# WiFi-Bee_v11.net
KiCad netlist of a schematic drawn in EAGLE
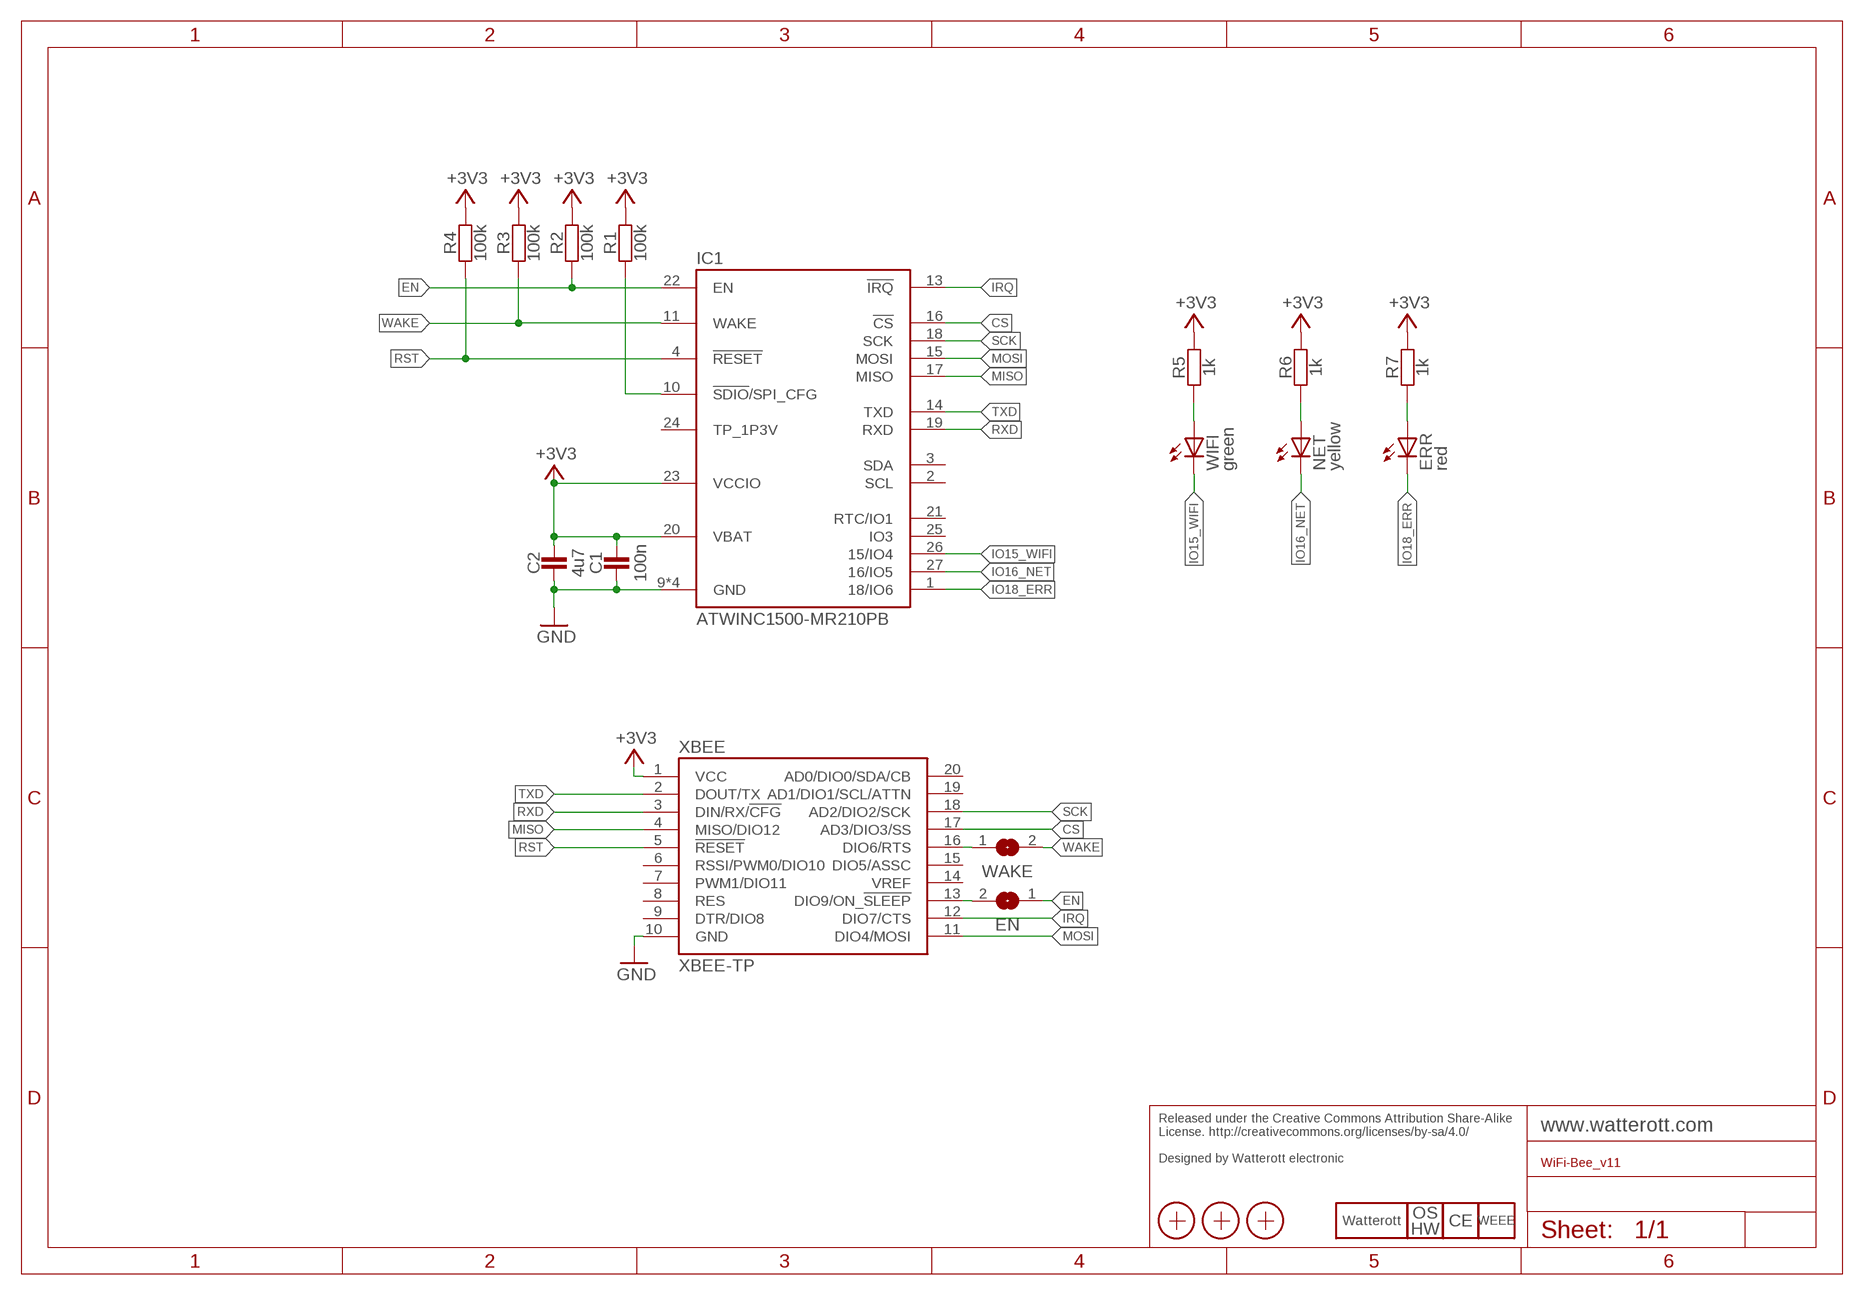
[diagram p0: schematic, sheet 1]

(export (version "E")
  (design (tool "Eeschema 10.0.6"))
  (components
    (comp (ref "C1")
      (value "100n")
      (footprint "eagle-import:C0402")
      (libsource (lib "eagle-import") (part "CAPACITOR-0402"))
    )
    (comp (ref "C2")
      (value "4u7")
      (footprint "eagle-import:C0402")
      (libsource (lib "eagle-import") (part "CAPACITOR-0402"))
    )
    (comp (ref "EN")
      (value "JUMPER2-0402")
      (footprint "eagle-import:JUMPER2-0402")
      (libsource (lib "eagle-import") (part "JUMPER2-0402"))
    )
    (comp (ref "ERR")
      (value "red")
      (footprint "eagle-import:C0603")
      (libsource (lib "eagle-import") (part "LED-0603"))
    )
    (comp (ref "IC1")
      (value "ATWINC1500-MR210PB")
      (footprint "eagle-import:ATWINC1500-MX210")
      (libsource (lib "eagle-import") (part "ATWINC1500-MR210PB"))
    )
    (comp (ref "LOGO1")
      (value "LOGO_CE-2")
      (footprint "eagle-import:CE_2MM")
      (libsource (lib "eagle-import") (part "LOGO_CE-2"))
    )
    (comp (ref "LOGO2")
      (value "LOGO_WEEE-4")
      (footprint "eagle-import:WEEE_4MM")
      (libsource (lib "eagle-import") (part "LOGO_WEEE-4"))
    )
    (comp (ref "LOGO3")
      (value "LOGO_SPARK-2")
      (footprint "eagle-import:SPARK_2MM")
      (libsource (lib "eagle-import") (part "LOGO_SPARK-2"))
    )
    (comp (ref "LOGO4")
      (value "LOGO_OSHW-2")
      (footprint "eagle-import:OSHW_2MM")
      (libsource (lib "eagle-import") (part "LOGO_OSHW-2"))
    )
    (comp (ref "NET")
      (value "yellow")
      (footprint "eagle-import:C0603")
      (libsource (lib "eagle-import") (part "LED-0603"))
    )
    (comp (ref "R1")
      (value "100k")
      (footprint "eagle-import:C0402")
      (libsource (lib "eagle-import") (part "RESISTOR-0402"))
    )
    (comp (ref "R2")
      (value "100k")
      (footprint "eagle-import:C0402")
      (libsource (lib "eagle-import") (part "RESISTOR-0402"))
    )
    (comp (ref "R3")
      (value "100k")
      (footprint "eagle-import:C0402")
      (libsource (lib "eagle-import") (part "RESISTOR-0402"))
    )
    (comp (ref "R4")
      (value "100k")
      (footprint "eagle-import:C0402")
      (libsource (lib "eagle-import") (part "RESISTOR-0402"))
    )
    (comp (ref "R5")
      (value "1k")
      (footprint "eagle-import:C0402")
      (libsource (lib "eagle-import") (part "RESISTOR-0402"))
    )
    (comp (ref "R6")
      (value "1k")
      (footprint "eagle-import:C0402")
      (libsource (lib "eagle-import") (part "RESISTOR-0402"))
    )
    (comp (ref "R7")
      (value "1k")
      (footprint "eagle-import:C0402")
      (libsource (lib "eagle-import") (part "RESISTOR-0402"))
    )
    (comp (ref "WAKE")
      (value "JUMPER2-0402")
      (footprint "eagle-import:JUMPER2-0402")
      (libsource (lib "eagle-import") (part "JUMPER2-0402"))
    )
    (comp (ref "WIFI")
      (value "green")
      (footprint "eagle-import:C0603")
      (libsource (lib "eagle-import") (part "LED-0603"))
    )
    (comp (ref "X1")
      (value "PASSER-07")
      (footprint "eagle-import:PASSER_07MM")
      (libsource (lib "eagle-import") (part "PASSER-07"))
    )
    (comp (ref "X2")
      (value "PASSER-07")
      (footprint "eagle-import:PASSER_07MM")
      (libsource (lib "eagle-import") (part "PASSER-07"))
    )
    (comp (ref "X3")
      (value "PASSER-07")
      (footprint "eagle-import:PASSER_07MM")
      (libsource (lib "eagle-import") (part "PASSER-07"))
    )
    (comp (ref "XBEE")
      (value "XBEE-TP")
      (footprint "eagle-import:XBEE_TP")
      (libsource (lib "eagle-import") (part "XBEE-TP"))
    )
  )
  (nets
    (net (code "1") (name "+3V3") (class "Default")
      (node (ref "C1") (pin "2") (pinfunction "2_2") (pintype "passive"))
      (node (ref "C2") (pin "2") (pinfunction "2_2") (pintype "passive"))
      (node (ref "IC1") (pin "20") (pinfunction "VBAT_20") (pintype "power_in"))
      (node (ref "IC1") (pin "23") (pinfunction "VCCIO_23") (pintype "power_in"))
      (node (ref "R1") (pin "2") (pinfunction "2_2") (pintype "passive"))
      (node (ref "R2") (pin "2") (pinfunction "2_2") (pintype "passive"))
      (node (ref "R3") (pin "2") (pinfunction "2_2") (pintype "passive"))
      (node (ref "R4") (pin "2") (pinfunction "2_2") (pintype "passive"))
      (node (ref "R5") (pin "2") (pinfunction "2_2") (pintype "passive"))
      (node (ref "R6") (pin "2") (pinfunction "2_2") (pintype "passive"))
      (node (ref "R7") (pin "2") (pinfunction "2_2") (pintype "passive"))
      (node (ref "XBEE") (pin "1") (pinfunction "VCC_1") (pintype "power_in"))
    )
    (net (code "2") (name "CS") (class "Default")
      (node (ref "IC1") (pin "16") (pinfunction "~{CS}_16") (pintype "input"))
      (node (ref "XBEE") (pin "17") (pinfunction "AD3/DIO3/SS_17") (pintype "bidirectional"))
    )
    (net (code "3") (name "EN") (class "Default")
      (node (ref "EN") (pin "1") (pinfunction "1_1") (pintype "passive"))
      (node (ref "IC1") (pin "22") (pinfunction "EN_22") (pintype "input"))
      (node (ref "R2") (pin "1") (pinfunction "1_1") (pintype "passive"))
    )
    (net (code "4") (name "GND") (class "Default")
      (node (ref "C1") (pin "1") (pinfunction "1_1") (pintype "passive"))
      (node (ref "C2") (pin "1") (pinfunction "1_1") (pintype "passive"))
      (node (ref "IC1") (pin "12") (pinfunction "GND_12") (pintype "power_in"))
      (node (ref "IC1") (pin "28") (pinfunction "GND_28") (pintype "power_in"))
      (node (ref "IC1") (pin "9") (pinfunction "GND_9") (pintype "power_in"))
      (node (ref "IC1") (pin "GND") (pinfunction "GND_GND") (pintype "power_in"))
      (node (ref "XBEE") (pin "10") (pinfunction "GND_10") (pintype "power_in"))
    )
    (net (code "5") (name "IO15_WIFI") (class "Default")
      (node (ref "IC1") (pin "26") (pinfunction "15/IO4_26") (pintype "bidirectional"))
      (node (ref "WIFI") (pin "C") (pinfunction "C_C") (pintype "passive"))
    )
    (net (code "6") (name "IO16_NET") (class "Default")
      (node (ref "IC1") (pin "27") (pinfunction "16/IO5_27") (pintype "bidirectional"))
      (node (ref "NET") (pin "C") (pinfunction "C_C") (pintype "passive"))
    )
    (net (code "7") (name "IO18_ERR") (class "Default")
      (node (ref "ERR") (pin "C") (pinfunction "C_C") (pintype "passive"))
      (node (ref "IC1") (pin "1") (pinfunction "18/IO6_1") (pintype "bidirectional"))
    )
    (net (code "8") (name "IRQ") (class "Default")
      (node (ref "IC1") (pin "13") (pinfunction "~{IRQ}_13") (pintype "output"))
      (node (ref "XBEE") (pin "12") (pinfunction "DIO7/CTS_12") (pintype "bidirectional"))
    )
    (net (code "9") (name "MISO") (class "Default")
      (node (ref "IC1") (pin "17") (pinfunction "MISO_17") (pintype "output"))
      (node (ref "XBEE") (pin "4") (pinfunction "MISO/DIO12_4") (pintype "bidirectional"))
    )
    (net (code "10") (name "MOSI") (class "Default")
      (node (ref "IC1") (pin "15") (pinfunction "MOSI_15") (pintype "input"))
      (node (ref "XBEE") (pin "11") (pinfunction "DIO4/MOSI_11") (pintype "bidirectional"))
    )
    (net (code "11") (name "Net-(ERR-PadA)") (class "Default")
      (node (ref "ERR") (pin "A") (pinfunction "A_A") (pintype "passive"))
      (node (ref "R7") (pin "1") (pinfunction "1_1") (pintype "passive"))
    )
    (net (code "12") (name "Net-(IC1-~{SDIO}{slash}SPI_CFG)") (class "Default")
      (node (ref "IC1") (pin "10") (pinfunction "~{SDIO}/SPI_CFG_10") (pintype "input"))
      (node (ref "R1") (pin "1") (pinfunction "1_1") (pintype "passive"))
    )
    (net (code "13") (name "Net-(NET-PadA)") (class "Default")
      (node (ref "NET") (pin "A") (pinfunction "A_A") (pintype "passive"))
      (node (ref "R6") (pin "1") (pinfunction "1_1") (pintype "passive"))
    )
    (net (code "14") (name "Net-(R5-Pad1)") (class "Default")
      (node (ref "R5") (pin "1") (pinfunction "1_1") (pintype "passive"))
      (node (ref "WIFI") (pin "A") (pinfunction "A_A") (pintype "passive"))
    )
    (net (code "15") (name "Net-(XBEE-DIO6{slash}RTS)") (class "Default")
      (node (ref "WAKE") (pin "1") (pinfunction "1_1") (pintype "passive"))
      (node (ref "XBEE") (pin "16") (pinfunction "DIO6/RTS_16") (pintype "bidirectional"))
    )
    (net (code "16") (name "Net-(XBEE-DIO9{slash}ON_~{SLEEP})") (class "Default")
      (node (ref "EN") (pin "2") (pinfunction "2_2") (pintype "passive"))
      (node (ref "XBEE") (pin "13") (pinfunction "DIO9/ON_~{SLEEP}_13") (pintype "bidirectional"))
    )
    (net (code "17") (name "RST") (class "Default")
      (node (ref "IC1") (pin "4") (pinfunction "~{RESET}_4") (pintype "input"))
      (node (ref "R4") (pin "1") (pinfunction "1_1") (pintype "passive"))
      (node (ref "XBEE") (pin "5") (pinfunction "~{RESET}_5") (pintype "bidirectional"))
    )
    (net (code "18") (name "RXD") (class "Default")
      (node (ref "IC1") (pin "19") (pinfunction "RXD_19") (pintype "input"))
      (node (ref "XBEE") (pin "3") (pinfunction "DIN/RX/~{CFG}_3") (pintype "bidirectional"))
    )
    (net (code "19") (name "SCK") (class "Default")
      (node (ref "IC1") (pin "18") (pinfunction "SCK_18") (pintype "input"))
      (node (ref "XBEE") (pin "18") (pinfunction "AD2/DIO2/SCK_18") (pintype "bidirectional"))
    )
    (net (code "20") (name "TXD") (class "Default")
      (node (ref "IC1") (pin "14") (pinfunction "TXD_14") (pintype "output"))
      (node (ref "XBEE") (pin "2") (pinfunction "DOUT/TX_2") (pintype "bidirectional"))
    )
    (net (code "21") (name "WAKE") (class "Default")
      (node (ref "IC1") (pin "11") (pinfunction "WAKE_11") (pintype "input"))
      (node (ref "R3") (pin "1") (pinfunction "1_1") (pintype "passive"))
      (node (ref "WAKE") (pin "2") (pinfunction "2_2") (pintype "passive"))
    )
    (net (code "22") (name "unconnected-(IC1-IO3-Pad25)") (class "Default")
      (node (ref "IC1") (pin "25") (pinfunction "IO3_25") (pintype "bidirectional"))
    )
    (net (code "23") (name "unconnected-(IC1-RTC{slash}IO1-Pad21)") (class "Default")
      (node (ref "IC1") (pin "21") (pinfunction "RTC/IO1_21") (pintype "bidirectional"))
    )
    (net (code "24") (name "unconnected-(IC1-SCL-Pad2)") (class "Default")
      (node (ref "IC1") (pin "2") (pinfunction "SCL_2") (pintype "bidirectional"))
    )
    (net (code "25") (name "unconnected-(IC1-SDA-Pad3)") (class "Default")
      (node (ref "IC1") (pin "3") (pinfunction "SDA_3") (pintype "bidirectional"))
    )
    (net (code "26") (name "unconnected-(IC1-TP_1P3V-Pad24)") (class "Default")
      (node (ref "IC1") (pin "24") (pinfunction "TP_1P3V_24") (pintype "bidirectional"))
    )
    (net (code "27") (name "unconnected-(XBEE-AD0{slash}DIO0{slash}SDA{slash}CB-Pad20)") (class "Default")
      (node (ref "XBEE") (pin "20") (pinfunction "AD0/DIO0/SDA/CB_20") (pintype "bidirectional"))
    )
    (net (code "28") (name "unconnected-(XBEE-AD1{slash}DIO1{slash}SCL{slash}ATTN-Pad19)") (class "Default")
      (node (ref "XBEE") (pin "19") (pinfunction "AD1/DIO1/SCL/ATTN_19") (pintype "bidirectional"))
    )
    (net (code "29") (name "unconnected-(XBEE-DIO5{slash}ASSC-Pad15)") (class "Default")
      (node (ref "XBEE") (pin "15") (pinfunction "DIO5/ASSC_15") (pintype "bidirectional"))
    )
    (net (code "30") (name "unconnected-(XBEE-DTR{slash}DIO8-Pad9)") (class "Default")
      (node (ref "XBEE") (pin "9") (pinfunction "DTR/DIO8_9") (pintype "bidirectional"))
    )
    (net (code "31") (name "unconnected-(XBEE-PWM1{slash}DIO11-Pad7)") (class "Default")
      (node (ref "XBEE") (pin "7") (pinfunction "PWM1/DIO11_7") (pintype "bidirectional"))
    )
    (net (code "32") (name "unconnected-(XBEE-RES-Pad8)") (class "Default")
      (node (ref "XBEE") (pin "8") (pinfunction "RES_8") (pintype "bidirectional"))
    )
    (net (code "33") (name "unconnected-(XBEE-RSSI{slash}PWM0{slash}DIO10-Pad6)") (class "Default")
      (node (ref "XBEE") (pin "6") (pinfunction "RSSI/PWM0/DIO10_6") (pintype "bidirectional"))
    )
    (net (code "34") (name "unconnected-(XBEE-VREF-Pad14)") (class "Default")
      (node (ref "XBEE") (pin "14") (pinfunction "VREF_14") (pintype "bidirectional"))
    )
  )
)
